# Adafruit_Qwiic_Stemma_QT_Breakout.net
KiCad netlist of a schematic drawn in EAGLE
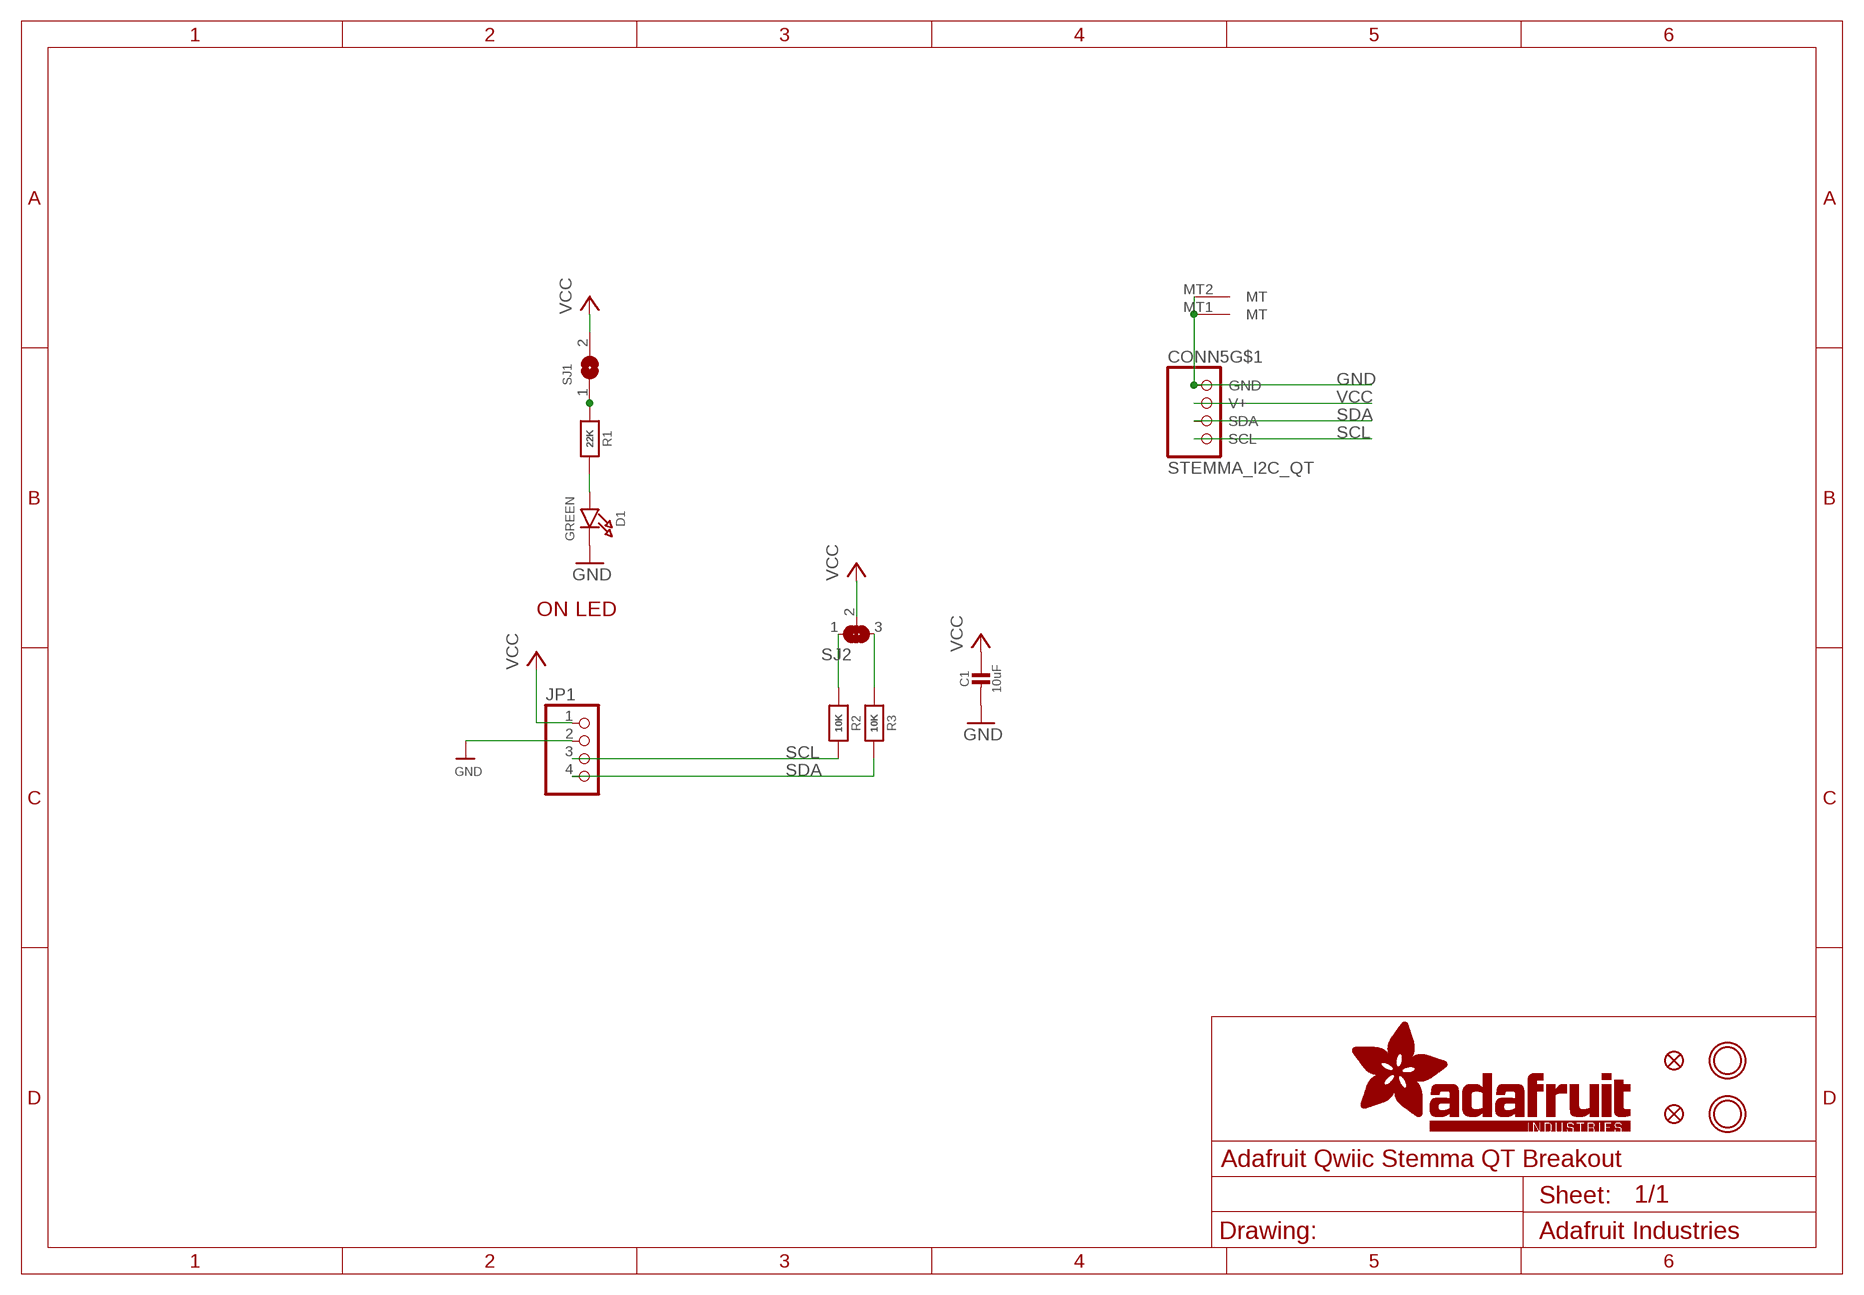
[diagram p0: schematic, sheet 1]

(export (version "E")
  (design (tool "Eeschema 10.0.6"))
  (components
    (comp (ref "C1")
      (value "10uF")
      (footprint "eagle-import:0805-NO")
      (libsource (lib "eagle-import") (part "CAP_CERAMIC0805-NOOUTLINE"))
    )
    (comp (ref "CONN5")
      (value "STEMMA_I2C_QT")
      (footprint "eagle-import:JST_SH4")
      (libsource (lib "eagle-import") (part "STEMMA_I2C_QT"))
    )
    (comp (ref "D1")
      (value "GREEN")
      (footprint "eagle-import:CHIPLED_0603_NOOUTLINE")
      (libsource (lib "eagle-import") (part "LED0603_NOOUTLINE"))
    )
    (comp (ref "FID3")
      (value "FIDUCIAL_1MM")
      (footprint "eagle-import:FIDUCIAL_1MM")
      (libsource (lib "eagle-import") (part "FIDUCIAL_1MM"))
    )
    (comp (ref "FID4")
      (value "FIDUCIAL_1MM")
      (footprint "eagle-import:FIDUCIAL_1MM")
      (libsource (lib "eagle-import") (part "FIDUCIAL_1MM"))
    )
    (comp (ref "JP1")
      (value "HEADER-1X476MIL")
      (footprint "eagle-import:1X04_ROUND_76")
      (libsource (lib "eagle-import") (part "HEADER-1X476MIL"))
    )
    (comp (ref "R1")
      (value "22K")
      (footprint "eagle-import:0603-NO")
      (libsource (lib "eagle-import") (part "RESISTOR_0603_NOOUT"))
    )
    (comp (ref "R2")
      (value "10K")
      (footprint "eagle-import:0603-NO")
      (libsource (lib "eagle-import") (part "RESISTOR_0603_NOOUT"))
    )
    (comp (ref "R3")
      (value "10K")
      (footprint "eagle-import:0603-NO")
      (libsource (lib "eagle-import") (part "RESISTOR_0603_NOOUT"))
    )
    (comp (ref "SJ1")
      (value "SOLDERJUMPERCLOSED")
      (footprint "eagle-import:SOLDERJUMPER_CLOSEDWIRE")
      (libsource (lib "eagle-import") (part "SOLDERJUMPERCLOSED"))
    )
    (comp (ref "SJ2")
      (value "SOLDERJUMPER_2WAY")
      (footprint "eagle-import:SOLDERJUMPER_2WAY_OPEN_NOPASTE")
      (libsource (lib "eagle-import") (part "SOLDERJUMPER_2WAY"))
    )
    (comp (ref "U$1")
      (value "MOUNTINGHOLE2.5")
      (footprint "eagle-import:MOUNTINGHOLE_2.5_PLATED")
      (libsource (lib "eagle-import") (part "MOUNTINGHOLE2.5"))
    )
    (comp (ref "U$17")
      (value "MOUNTINGHOLE2.5")
      (footprint "eagle-import:MOUNTINGHOLE_2.5_PLATED")
      (libsource (lib "eagle-import") (part "MOUNTINGHOLE2.5"))
    )
  )
  (nets
    (net (code "1") (name "/SCL") (class "Default")
      (node (ref "CONN5") (pin "4") (pinfunction "SCL_4") (pintype "passive"))
      (node (ref "JP1") (pin "3") (pinfunction "3_3") (pintype "passive"))
      (node (ref "R2") (pin "2") (pinfunction "2_2") (pintype "passive"))
    )
    (net (code "2") (name "/SDA") (class "Default")
      (node (ref "CONN5") (pin "3") (pinfunction "SDA_3") (pintype "passive"))
      (node (ref "JP1") (pin "4") (pinfunction "4_4") (pintype "passive"))
      (node (ref "R3") (pin "2") (pinfunction "2_2") (pintype "passive"))
    )
    (net (code "3") (name "GND") (class "Default")
      (node (ref "C1") (pin "2") (pinfunction "2_2") (pintype "passive"))
      (node (ref "CONN5") (pin "1") (pinfunction "GND_1") (pintype "passive"))
      (node (ref "CONN5") (pin "MT1") (pinfunction "MT_MT1") (pintype "bidirectional"))
      (node (ref "CONN5") (pin "MT2") (pinfunction "MT_MT2") (pintype "bidirectional"))
      (node (ref "D1") (pin "C") (pinfunction "C_C") (pintype "passive"))
      (node (ref "JP1") (pin "2") (pinfunction "2_2") (pintype "passive"))
    )
    (net (code "4") (name "Net-(D1-PadA)") (class "Default")
      (node (ref "D1") (pin "A") (pinfunction "A_A") (pintype "passive"))
      (node (ref "R1") (pin "2") (pinfunction "2_2") (pintype "passive"))
    )
    (net (code "5") (name "Net-(R1-Pad1)") (class "Default")
      (node (ref "R1") (pin "1") (pinfunction "1_1") (pintype "passive"))
      (node (ref "SJ1") (pin "1") (pinfunction "1_1") (pintype "passive"))
    )
    (net (code "6") (name "Net-(R2-Pad1)") (class "Default")
      (node (ref "R2") (pin "1") (pinfunction "1_1") (pintype "passive"))
      (node (ref "SJ2") (pin "1") (pinfunction "1_1") (pintype "passive"))
    )
    (net (code "7") (name "Net-(R3-Pad1)") (class "Default")
      (node (ref "R3") (pin "1") (pinfunction "1_1") (pintype "passive"))
      (node (ref "SJ2") (pin "3") (pinfunction "3_3") (pintype "passive"))
    )
    (net (code "8") (name "VCC") (class "Default")
      (node (ref "C1") (pin "1") (pinfunction "1_1") (pintype "passive"))
      (node (ref "CONN5") (pin "2") (pinfunction "V+_2") (pintype "passive"))
      (node (ref "JP1") (pin "1") (pinfunction "1_1") (pintype "passive"))
      (node (ref "SJ1") (pin "2") (pinfunction "2_2") (pintype "passive"))
      (node (ref "SJ2") (pin "2") (pinfunction "2_2") (pintype "passive"))
    )
  )
)
